# RS485_R232.net
KiCad netlist of a schematic drawn in Altium Designer
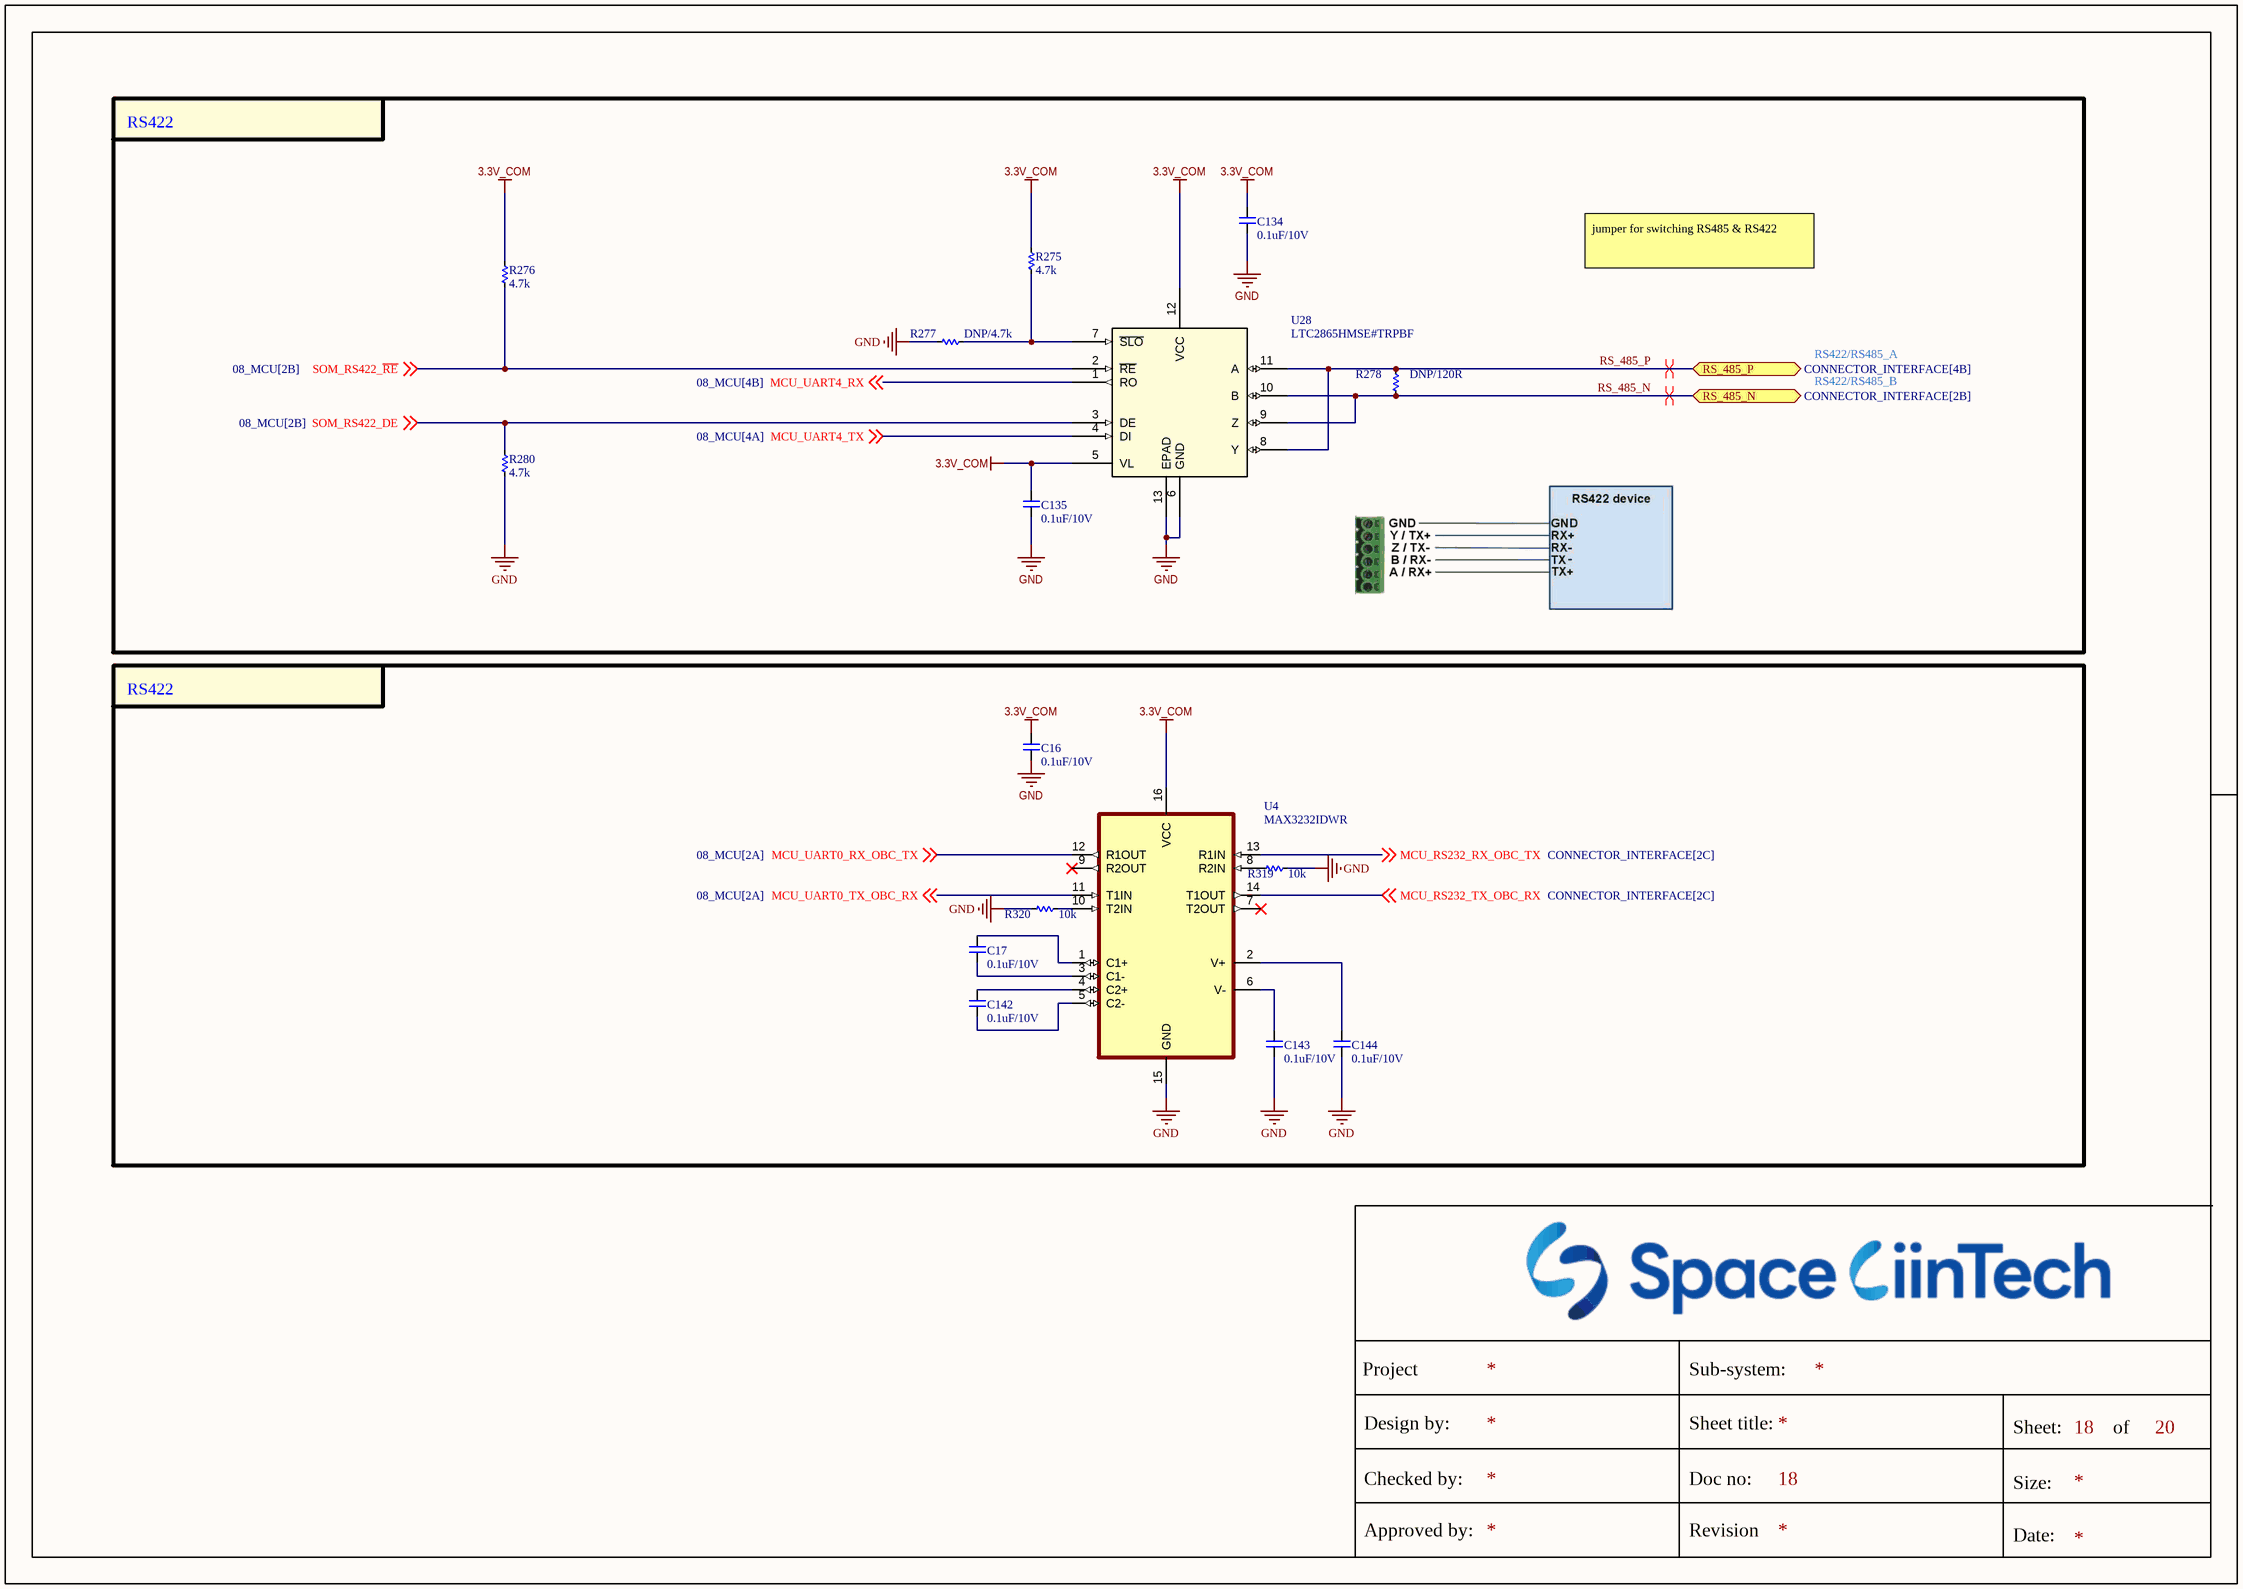
[diagram p0: RS485_R232.SchDoc]

(export (version "E")
  (design (tool "Eeschema 10.0.6"))
  (components
    (comp (ref "C16")
      (value "0.1uF/10V")
      (footprint "CAP_C_1005X50_L")
      (description "CAP")
      (libsource (lib "LABLIB") (part "_CAP_C_2"))
    )
    (comp (ref "C17")
      (value "0.1uF/10V")
      (footprint "CAP_C_1005X50_L")
      (description "CAP")
      (libsource (lib "LABLIB") (part "_CAP_C_2"))
    )
    (comp (ref "C134")
      (value "0.1uF/10V")
      (footprint "CAP_C_1005X50_L")
      (description "CAP")
      (libsource (lib "LABLIB") (part "_CAP_C_2"))
    )
    (comp (ref "C135")
      (value "0.1uF/10V")
      (footprint "CAP_C_1005X50_L")
      (description "CAP")
      (libsource (lib "LABLIB") (part "_CAP_C_2"))
    )
    (comp (ref "C142")
      (value "0.1uF/10V")
      (footprint "CAP_C_1005X50_L")
      (description "CAP")
      (libsource (lib "LABLIB") (part "_CAP_C_2"))
    )
    (comp (ref "C143")
      (value "0.1uF/10V")
      (footprint "CAP_C_1005X50_L")
      (description "CAP")
      (libsource (lib "LABLIB") (part "_CAP_C_2"))
    )
    (comp (ref "C144")
      (value "0.1uF/10V")
      (footprint "CAP_C_1005X50_L")
      (description "CAP")
      (libsource (lib "LABLIB") (part "_CAP_C_2"))
    )
    (comp (ref "R275")
      (value "4.7k")
      (footprint "RES_C_1005x30_L")
      (description "RES")
      (libsource (lib "IFBschelib") (part "_RES_B_2"))
    )
    (comp (ref "R276")
      (value "4.7k")
      (footprint "RES_C_1005x30_L")
      (description "RES")
      (libsource (lib "IFBschelib") (part "_RES_B_2"))
    )
    (comp (ref "R277")
      (value "DNP/4.7k")
      (footprint "RES_C_1005x30_L")
      (description "RES")
      (libsource (lib "IFBschelib") (part "_RES_B_2"))
    )
    (comp (ref "R278")
      (value "DNP/120R")
      (footprint "RES_C_1005x30_L")
      (description "RES")
      (libsource (lib "IFBschelib") (part "_RES_B_2"))
    )
    (comp (ref "R280")
      (value "4.7k")
      (footprint "RES_C_1005x30_L")
      (description "RES")
      (libsource (lib "IFBschelib") (part "_RES_B_2"))
    )
    (comp (ref "R319")
      (value "10k")
      (footprint "RES_C_1005X40")
      (description "RES")
      (libsource (lib "LABLIB") (part "_RES_B_2"))
    )
    (comp (ref "R320")
      (value "10k")
      (footprint "RES_C_1005X40")
      (description "RES")
      (libsource (lib "LABLIB") (part "_RES_B_2"))
    )
    (comp (ref "U4")
      (value "MAX3232IDWR")
      (footprint "SOIC127P1032X265-16N")
      (description "3.0V to 5.5V, Low-Power, Up to 1Mbps, True RS-232 Transceivers")
      (fields (field (name "MF") "Analog Devices") (field (name "MP") "MAX3232CSE+T"))
      (libsource (lib "LABLIB") (part "IC_RS232_MAX3232IDWR"))
    )
    (comp (ref "U28")
      (value "LTC2865HMSE#TRPBF")
      (footprint "MSOP-12_MSE_LIT")
      (description "Â±60V Fault Protected 3V to 5.5V RS485/RS422 Transceivers")
      (fields (field (name "COPYRIGHT") "Copyright (C) 2025 Ultra Librarian. All rights reserved."))
      (libsource (lib "BEE-DAL_EXP_sche") (part "LTC2865HMSETRPBF"))
    )
  )
  (nets
    (net (code "1") (name "/RS_485_N") (class "Default")
      (node (ref "R278") (pin "2") (pinfunction "2_2") (pintype "passive"))
      (node (ref "U28") (pin "10") (pinfunction "B_10") (pintype "bidirectional"))
      (node (ref "U28") (pin "9") (pinfunction "Z_9") (pintype "bidirectional"))
    )
    (net (code "2") (name "/RS_485_P") (class "Default")
      (node (ref "R278") (pin "1") (pinfunction "1_1") (pintype "passive"))
      (node (ref "U28") (pin "11") (pinfunction "A_11") (pintype "bidirectional"))
      (node (ref "U28") (pin "8") (pinfunction "Y_8") (pintype "bidirectional"))
    )
    (net (code "3") (name "3.3V_COM") (class "Default")
      (node (ref "C134") (pin "2") (pinfunction "2_2") (pintype "passive"))
      (node (ref "C135") (pin "2") (pinfunction "2_2") (pintype "passive"))
      (node (ref "C16") (pin "2") (pinfunction "2_2") (pintype "passive"))
      (node (ref "R275") (pin "2") (pinfunction "2_2") (pintype "passive"))
      (node (ref "R276") (pin "2") (pinfunction "2_2") (pintype "passive"))
      (node (ref "U28") (pin "12") (pinfunction "VCC_12") (pintype "power_in"))
      (node (ref "U28") (pin "5") (pinfunction "VL_5") (pintype "power_in"))
      (node (ref "U4") (pin "16") (pinfunction "VCC_16") (pintype "power_in"))
    )
    (net (code "4") (name "GND") (class "Default")
      (node (ref "C134") (pin "1") (pinfunction "1_1") (pintype "passive"))
      (node (ref "C135") (pin "1") (pinfunction "1_1") (pintype "passive"))
      (node (ref "C143") (pin "1") (pinfunction "1_1") (pintype "passive"))
      (node (ref "C144") (pin "1") (pinfunction "1_1") (pintype "passive"))
      (node (ref "C16") (pin "1") (pinfunction "1_1") (pintype "passive"))
      (node (ref "R277") (pin "2") (pinfunction "2_2") (pintype "passive"))
      (node (ref "R280") (pin "1") (pinfunction "1_1") (pintype "passive"))
      (node (ref "R319") (pin "1") (pinfunction "1_1") (pintype "passive"))
      (node (ref "R320") (pin "1") (pinfunction "1_1") (pintype "passive"))
      (node (ref "U28") (pin "13") (pinfunction "EPAD_13") (pintype "passive"))
      (node (ref "U28") (pin "6") (pinfunction "GND_6") (pintype "power_in"))
      (node (ref "U4") (pin "15") (pinfunction "GND_15") (pintype "power_in"))
    )
    (net (code "5") (name "MCU_RS232_RX_OBC_TX") (class "Default")
      (node (ref "U4") (pin "13") (pinfunction "R1IN_13") (pintype "input"))
    )
    (net (code "6") (name "MCU_RS232_TX_OBC_RX") (class "Default")
      (node (ref "U4") (pin "14") (pinfunction "T1OUT_14") (pintype "output"))
    )
    (net (code "7") (name "MCU_UART0_RX_OBC_TX") (class "Default")
      (node (ref "U4") (pin "12") (pinfunction "R1OUT_12") (pintype "output"))
    )
    (net (code "8") (name "MCU_UART0_TX_OBC_RX") (class "Default")
      (node (ref "U4") (pin "11") (pinfunction "T1IN_11") (pintype "input"))
    )
    (net (code "9") (name "MCU_UART4_RX") (class "Default")
      (node (ref "U28") (pin "1") (pinfunction "RO_1") (pintype "output"))
    )
    (net (code "10") (name "MCU_UART4_TX") (class "Default")
      (node (ref "U28") (pin "4") (pinfunction "DI_4") (pintype "input"))
    )
    (net (code "11") (name "Net-(U4-C1+)") (class "Default")
      (node (ref "C17") (pin "2") (pinfunction "2_2") (pintype "passive"))
      (node (ref "U4") (pin "1") (pinfunction "C1+_1") (pintype "bidirectional"))
    )
    (net (code "12") (name "Net-(U4-C1-)") (class "Default")
      (node (ref "C17") (pin "1") (pinfunction "1_1") (pintype "passive"))
      (node (ref "U4") (pin "3") (pinfunction "C1-_3") (pintype "bidirectional"))
    )
    (net (code "13") (name "Net-(U4-C2+)") (class "Default")
      (node (ref "C142") (pin "2") (pinfunction "2_2") (pintype "passive"))
      (node (ref "U4") (pin "4") (pinfunction "C2+_4") (pintype "bidirectional"))
    )
    (net (code "14") (name "Net-(U4-C2-)") (class "Default")
      (node (ref "C142") (pin "1") (pinfunction "1_1") (pintype "passive"))
      (node (ref "U4") (pin "5") (pinfunction "C2-_5") (pintype "bidirectional"))
    )
    (net (code "15") (name "Net-(U4-R2IN)") (class "Default")
      (node (ref "R319") (pin "2") (pinfunction "2_2") (pintype "passive"))
      (node (ref "U4") (pin "8") (pinfunction "R2IN_8") (pintype "input"))
    )
    (net (code "16") (name "Net-(U4-T2IN)") (class "Default")
      (node (ref "R320") (pin "2") (pinfunction "2_2") (pintype "passive"))
      (node (ref "U4") (pin "10") (pinfunction "T2IN_10") (pintype "input"))
    )
    (net (code "17") (name "Net-(U4-V+)") (class "Default")
      (node (ref "C144") (pin "2") (pinfunction "2_2") (pintype "passive"))
      (node (ref "U4") (pin "2") (pinfunction "V+_2") (pintype "power_in"))
    )
    (net (code "18") (name "Net-(U4-V-)") (class "Default")
      (node (ref "C143") (pin "2") (pinfunction "2_2") (pintype "passive"))
      (node (ref "U4") (pin "6") (pinfunction "V-_6") (pintype "power_in"))
    )
    (net (code "19") (name "Net-(U28-~{SLO})") (class "Default")
      (node (ref "R275") (pin "1") (pinfunction "1_1") (pintype "passive"))
      (node (ref "R277") (pin "1") (pinfunction "1_1") (pintype "passive"))
      (node (ref "U28") (pin "7") (pinfunction "~{SLO}_7") (pintype "input"))
    )
    (net (code "20") (name "SOM_RS422_DE") (class "Default")
      (node (ref "R280") (pin "2") (pinfunction "2_2") (pintype "passive"))
      (node (ref "U28") (pin "3") (pinfunction "DE_3") (pintype "input"))
    )
    (net (code "21") (name "SOM_RS422_~{RE}") (class "Default")
      (node (ref "R276") (pin "1") (pinfunction "1_1") (pintype "passive"))
      (node (ref "U28") (pin "2") (pinfunction "~{RE}_2") (pintype "input"))
    )
    (net (code "22") (name "unconnected-(U4-R2OUT-Pad9)") (class "Default")
      (node (ref "U4") (pin "9") (pinfunction "R2OUT_9") (pintype "output+no_connect"))
    )
    (net (code "23") (name "unconnected-(U4-T2OUT-Pad7)") (class "Default")
      (node (ref "U4") (pin "7") (pinfunction "T2OUT_7") (pintype "output+no_connect"))
    )
  )
)
